# PWR.net
KiCad netlist of a schematic drawn in Altium Designer
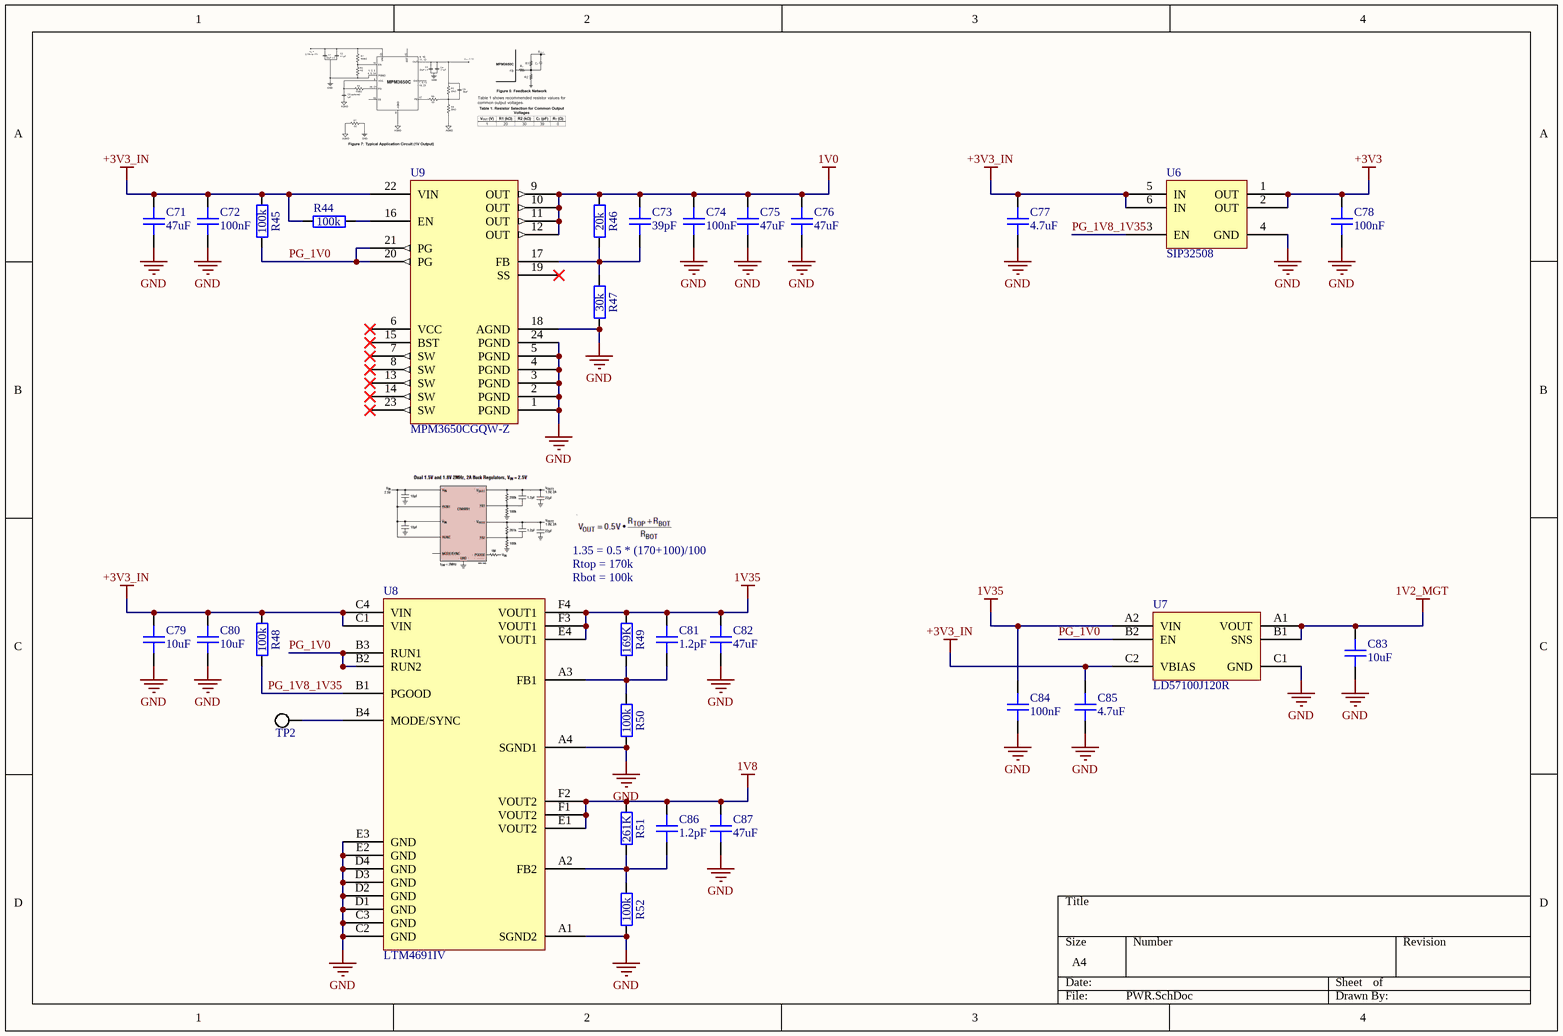
[diagram p0: PWR.SchDoc]

(export (version "E")
  (design (tool "Eeschema 10.0.6"))
  (components
    (comp (ref "C71")
      (value "47uF")
      (footprint "GEN_C_0805")
      (libsource (lib "DSO") (part "CAP 47uF 6.3V X5R 0805"))
    )
    (comp (ref "C72")
      (value "100nF")
      (footprint "GEN_C_0402")
      (libsource (lib "DSO") (part "CAP 100nF 16V X7R 0402"))
    )
    (comp (ref "C73")
      (value "39pF")
      (footprint "GEN_C_0402")
      (libsource (lib "DSO") (part "CAP 39pF 50V C0G 0402"))
    )
    (comp (ref "C74")
      (value "100nF")
      (footprint "GEN_C_0402")
      (libsource (lib "DSO") (part "CAP 100nF 16V X7R 0402"))
    )
    (comp (ref "C75")
      (value "47uF")
      (footprint "GEN_C_0805")
      (libsource (lib "DSO") (part "CAP 47uF 6.3V X5R 0805"))
    )
    (comp (ref "C76")
      (value "47uF")
      (footprint "GEN_C_0805")
      (libsource (lib "DSO") (part "CAP 47uF 6.3V X5R 0805"))
    )
    (comp (ref "C77")
      (value "4.7uF")
      (footprint "GEN_C_0402")
      (libsource (lib "DSO") (part "CAP 4.7uF 6.3V X5R 0402"))
    )
    (comp (ref "C78")
      (value "100nF")
      (footprint "GEN_C_0402")
      (libsource (lib "DSO") (part "CAP 100nF 16V X7R 0402"))
    )
    (comp (ref "C79")
      (value "10uF")
      (footprint "GEN_C_0603")
      (libsource (lib "DSO") (part "CAP 10uF 10V X5R 0603"))
    )
    (comp (ref "C80")
      (value "10uF")
      (footprint "GEN_C_0603")
      (libsource (lib "DSO") (part "CAP 10uF 10V X5R 0603"))
    )
    (comp (ref "C81")
      (value "1.2pF")
      (footprint "GEN_C_0402")
      (libsource (lib "DSO") (part "CAP 1.2pF 50V C0G 0402"))
    )
    (comp (ref "C82")
      (value "47uF")
      (footprint "GEN_C_0805")
      (libsource (lib "DSO") (part "CAP 47uF 6.3V X5R 0805"))
    )
    (comp (ref "C83")
      (value "10uF")
      (footprint "GEN_C_0603")
      (libsource (lib "DSO") (part "CAP 10uF 10V X5R 0603"))
    )
    (comp (ref "C84")
      (value "100nF")
      (footprint "GEN_C_0402")
      (libsource (lib "DSO") (part "CAP 100nF 16V X7R 0402"))
    )
    (comp (ref "C85")
      (value "4.7uF")
      (footprint "GEN_C_0402")
      (libsource (lib "DSO") (part "CAP 4.7uF 6.3V X5R 0402"))
    )
    (comp (ref "C86")
      (value "1.2pF")
      (footprint "GEN_C_0402")
      (libsource (lib "DSO") (part "CAP 1.2pF 50V C0G 0402"))
    )
    (comp (ref "C87")
      (value "47uF")
      (footprint "GEN_C_0805")
      (libsource (lib "DSO") (part "CAP 47uF 6.3V X5R 0805"))
    )
    (comp (ref "R44")
      (value "100k")
      (footprint "GEN_R_0402")
      (fields (field (name "TOLERANCE") "1%"))
      (libsource (lib "") (part "RES 100K OHM 1% 1/10W 0402_1"))
    )
    (comp (ref "R45")
      (value "100k")
      (footprint "GEN_R_0402")
      (fields (field (name "TOLERANCE") "1%"))
      (libsource (lib "DSO") (part "RES 100K OHM 1% 1/10W 0402"))
    )
    (comp (ref "R46")
      (value "20k")
      (footprint "GEN_R_0402")
      (fields (field (name "TOLERANCE") "1%"))
      (libsource (lib "DSO") (part "RES 20K OHM 1% 1/16W 0402"))
    )
    (comp (ref "R47")
      (value "30k")
      (footprint "GEN_R_0402")
      (fields (field (name "TOLERANCE") "1%"))
      (libsource (lib "DSO") (part "RES 30K OHM 1% 1/16W 0402"))
    )
    (comp (ref "R48")
      (value "100k")
      (footprint "GEN_R_0402")
      (fields (field (name "TOLERANCE") "1%"))
      (libsource (lib "DSO") (part "RES 100K OHM 1% 1/10W 0402"))
    )
    (comp (ref "R49")
      (value "169K")
      (footprint "GEN_R_0402")
      (fields (field (name "TOLERANCE") "1%"))
      (libsource (lib "DSO") (part "RES 169K OHM 1% 1/16W 0402"))
    )
    (comp (ref "R50")
      (value "100k")
      (footprint "GEN_R_0402")
      (fields (field (name "TOLERANCE") "1%"))
      (libsource (lib "DSO") (part "RES 100K OHM 1% 1/10W 0402"))
    )
    (comp (ref "R51")
      (value "261K")
      (footprint "GEN_R_0402")
      (fields (field (name "TOLERANCE") "1%"))
      (libsource (lib "DSO") (part "RES 261K OHM 1% 1/16W 0402"))
    )
    (comp (ref "R52")
      (value "100k")
      (footprint "GEN_R_0402")
      (fields (field (name "TOLERANCE") "1%"))
      (libsource (lib "DSO") (part "RES 100K OHM 1% 1/10W 0402"))
    )
    (comp (ref "TP2") (value "PCB") (footprint "GEN_TP_PCB") (libsource (lib "DSO") (part "TP PCB 1mm")))
    (comp (ref "U6")
      (value "SIP32508")
      (footprint "VISH_TSOT6")
      (libsource (lib "DSO") (part "IC SWITCH LOAD SIP32508"))
    )
    (comp (ref "U7")
      (value "LD57100J120R")
      (footprint "ST_FlipChip6")
      (libsource (lib "DSO") (part "IC LDO LD57100J120R"))
    )
    (comp (ref "U8")
      (value "LTM4691IV")
      (footprint "AD_LGA24")
      (libsource (lib "DSO") (part "IC BUCK LTM4691IV"))
    )
    (comp (ref "U9")
      (value "MPM3650CGQW-Z")
      (footprint "MPS_MPM3650")
      (libsource (lib "DSO") (part "IC BUCK MPM3650CGQW-Z"))
    )
  )
  (nets
    (net (code "1") (name "+3V3") (class "Default")
      (node (ref "C78") (pin "2") (pinfunction "2_2") (pintype "passive"))
      (node (ref "U6") (pin "1") (pinfunction "OUT_1") (pintype "passive"))
      (node (ref "U6") (pin "2") (pinfunction "OUT_2") (pintype "passive"))
    )
    (net (code "2") (name "+3V3_IN") (class "Default")
      (node (ref "C71") (pin "2") (pinfunction "2_2") (pintype "passive"))
      (node (ref "C72") (pin "2") (pinfunction "2_2") (pintype "passive"))
      (node (ref "C77") (pin "2") (pinfunction "2_2") (pintype "passive"))
      (node (ref "C79") (pin "2") (pinfunction "2_2") (pintype "passive"))
      (node (ref "C80") (pin "2") (pinfunction "2_2") (pintype "passive"))
      (node (ref "C85") (pin "2") (pinfunction "2_2") (pintype "passive"))
      (node (ref "R44") (pin "1") (pinfunction "1_1") (pintype "passive"))
      (node (ref "R45") (pin "2") (pinfunction "2_2") (pintype "passive"))
      (node (ref "R48") (pin "2") (pinfunction "2_2") (pintype "passive"))
      (node (ref "U6") (pin "5") (pinfunction "IN_5") (pintype "passive"))
      (node (ref "U6") (pin "6") (pinfunction "IN_6") (pintype "passive"))
      (node (ref "U7") (pin "C2") (pinfunction "VBIAS_C2") (pintype "passive"))
      (node (ref "U8") (pin "C1") (pinfunction "VIN_C1") (pintype "passive"))
      (node (ref "U8") (pin "C4") (pinfunction "VIN_C4") (pintype "passive"))
      (node (ref "U9") (pin "22") (pinfunction "VIN_22") (pintype "power_in"))
    )
    (net (code "3") (name "/PG_1V0") (class "Default")
      (node (ref "R45") (pin "1") (pinfunction "1_1") (pintype "passive"))
      (node (ref "U7") (pin "B2") (pinfunction "EN_B2") (pintype "passive"))
      (node (ref "U8") (pin "B2") (pinfunction "RUN2_B2") (pintype "passive"))
      (node (ref "U8") (pin "B3") (pinfunction "RUN1_B3") (pintype "passive"))
      (node (ref "U9") (pin "20") (pinfunction "PG_20") (pintype "output"))
      (node (ref "U9") (pin "21") (pinfunction "PG_21") (pintype "output"))
    )
    (net (code "4") (name "/PG_1V8_1V35") (class "Default")
      (node (ref "R48") (pin "1") (pinfunction "1_1") (pintype "passive"))
      (node (ref "U6") (pin "3") (pinfunction "EN_3") (pintype "passive"))
      (node (ref "U8") (pin "B1") (pinfunction "PGOOD_B1") (pintype "passive"))
    )
    (net (code "5") (name "1V0") (class "Default")
      (node (ref "C73") (pin "2") (pinfunction "2_2") (pintype "passive"))
      (node (ref "C74") (pin "2") (pinfunction "2_2") (pintype "passive"))
      (node (ref "C75") (pin "2") (pinfunction "2_2") (pintype "passive"))
      (node (ref "C76") (pin "2") (pinfunction "2_2") (pintype "passive"))
      (node (ref "R46") (pin "2") (pinfunction "2_2") (pintype "passive"))
      (node (ref "U9") (pin "10") (pinfunction "OUT_10") (pintype "output"))
      (node (ref "U9") (pin "11") (pinfunction "OUT_11") (pintype "output"))
      (node (ref "U9") (pin "12") (pinfunction "OUT_12") (pintype "output"))
      (node (ref "U9") (pin "9") (pinfunction "OUT_9") (pintype "output"))
    )
    (net (code "6") (name "1V2_MGT") (class "Default")
      (node (ref "C83") (pin "2") (pinfunction "2_2") (pintype "passive"))
      (node (ref "U7") (pin "A1") (pinfunction "VOUT_A1") (pintype "passive"))
      (node (ref "U7") (pin "B1") (pinfunction "SNS_B1") (pintype "passive"))
    )
    (net (code "7") (name "1V8") (class "Default")
      (node (ref "C86") (pin "2") (pinfunction "2_2") (pintype "passive"))
      (node (ref "C87") (pin "2") (pinfunction "2_2") (pintype "passive"))
      (node (ref "R51") (pin "2") (pinfunction "2_2") (pintype "passive"))
      (node (ref "U8") (pin "E1") (pinfunction "VOUT2_E1") (pintype "passive"))
      (node (ref "U8") (pin "F1") (pinfunction "VOUT2_F1") (pintype "passive"))
      (node (ref "U8") (pin "F2") (pinfunction "VOUT2_F2") (pintype "passive"))
    )
    (net (code "8") (name "1V35") (class "Default")
      (node (ref "C81") (pin "2") (pinfunction "2_2") (pintype "passive"))
      (node (ref "C82") (pin "2") (pinfunction "2_2") (pintype "passive"))
      (node (ref "C84") (pin "2") (pinfunction "2_2") (pintype "passive"))
      (node (ref "R49") (pin "2") (pinfunction "2_2") (pintype "passive"))
      (node (ref "U7") (pin "A2") (pinfunction "VIN_A2") (pintype "passive"))
      (node (ref "U8") (pin "E4") (pinfunction "VOUT1_E4") (pintype "passive"))
      (node (ref "U8") (pin "F3") (pinfunction "VOUT1_F3") (pintype "passive"))
      (node (ref "U8") (pin "F4") (pinfunction "VOUT1_F4") (pintype "passive"))
    )
    (net (code "9") (name "GND") (class "Default")
      (node (ref "C71") (pin "1") (pinfunction "1_1") (pintype "passive"))
      (node (ref "C72") (pin "1") (pinfunction "1_1") (pintype "passive"))
      (node (ref "C74") (pin "1") (pinfunction "1_1") (pintype "passive"))
      (node (ref "C75") (pin "1") (pinfunction "1_1") (pintype "passive"))
      (node (ref "C76") (pin "1") (pinfunction "1_1") (pintype "passive"))
      (node (ref "C77") (pin "1") (pinfunction "1_1") (pintype "passive"))
      (node (ref "C78") (pin "1") (pinfunction "1_1") (pintype "passive"))
      (node (ref "C79") (pin "1") (pinfunction "1_1") (pintype "passive"))
      (node (ref "C80") (pin "1") (pinfunction "1_1") (pintype "passive"))
      (node (ref "C82") (pin "1") (pinfunction "1_1") (pintype "passive"))
      (node (ref "C83") (pin "1") (pinfunction "1_1") (pintype "passive"))
      (node (ref "C84") (pin "1") (pinfunction "1_1") (pintype "passive"))
      (node (ref "C85") (pin "1") (pinfunction "1_1") (pintype "passive"))
      (node (ref "C87") (pin "1") (pinfunction "1_1") (pintype "passive"))
      (node (ref "R47") (pin "1") (pinfunction "1_1") (pintype "passive"))
      (node (ref "R50") (pin "1") (pinfunction "1_1") (pintype "passive"))
      (node (ref "R52") (pin "1") (pinfunction "1_1") (pintype "passive"))
      (node (ref "U6") (pin "4") (pinfunction "GND_4") (pintype "passive"))
      (node (ref "U7") (pin "C1") (pinfunction "GND_C1") (pintype "passive"))
      (node (ref "U8") (pin "A1") (pinfunction "SGND2_A1") (pintype "passive"))
      (node (ref "U8") (pin "A4") (pinfunction "SGND1_A4") (pintype "passive"))
      (node (ref "U8") (pin "C2") (pinfunction "GND_C2") (pintype "passive"))
      (node (ref "U8") (pin "C3") (pinfunction "GND_C3") (pintype "passive"))
      (node (ref "U8") (pin "D1") (pinfunction "GND_D1") (pintype "passive"))
      (node (ref "U8") (pin "D2") (pinfunction "GND_D2") (pintype "passive"))
      (node (ref "U8") (pin "D3") (pinfunction "GND_D3") (pintype "passive"))
      (node (ref "U8") (pin "D4") (pinfunction "GND_D4") (pintype "passive"))
      (node (ref "U8") (pin "E2") (pinfunction "GND_E2") (pintype "passive"))
      (node (ref "U8") (pin "E3") (pinfunction "GND_E3") (pintype "passive"))
      (node (ref "U9") (pin "1") (pinfunction "PGND_1") (pintype "passive"))
      (node (ref "U9") (pin "18") (pinfunction "AGND_18") (pintype "passive"))
      (node (ref "U9") (pin "2") (pinfunction "PGND_2") (pintype "passive"))
      (node (ref "U9") (pin "24") (pinfunction "PGND_24") (pintype "passive"))
      (node (ref "U9") (pin "3") (pinfunction "PGND_3") (pintype "passive"))
      (node (ref "U9") (pin "4") (pinfunction "PGND_4") (pintype "passive"))
      (node (ref "U9") (pin "5") (pinfunction "PGND_5") (pintype "passive"))
    )
    (net (code "10") (name "Net-(U8-FB1)") (class "Default")
      (node (ref "C81") (pin "1") (pinfunction "1_1") (pintype "passive"))
      (node (ref "R49") (pin "1") (pinfunction "1_1") (pintype "passive"))
      (node (ref "R50") (pin "2") (pinfunction "2_2") (pintype "passive"))
      (node (ref "U8") (pin "A3") (pinfunction "FB1_A3") (pintype "passive"))
    )
    (net (code "11") (name "Net-(U8-FB2)") (class "Default")
      (node (ref "C86") (pin "1") (pinfunction "1_1") (pintype "passive"))
      (node (ref "R51") (pin "1") (pinfunction "1_1") (pintype "passive"))
      (node (ref "R52") (pin "2") (pinfunction "2_2") (pintype "passive"))
      (node (ref "U8") (pin "A2") (pinfunction "FB2_A2") (pintype "passive"))
    )
    (net (code "12") (name "Net-(U8-MODE{slash}SYNC)") (class "Default")
      (node (ref "TP2") (pin "1") (pinfunction "1_1") (pintype "passive"))
      (node (ref "U8") (pin "B4") (pinfunction "MODE/SYNC_B4") (pintype "passive"))
    )
    (net (code "13") (name "Net-(U9-EN)") (class "Default")
      (node (ref "R44") (pin "2") (pinfunction "2_2") (pintype "passive"))
      (node (ref "U9") (pin "16") (pinfunction "EN_16") (pintype "passive"))
    )
    (net (code "14") (name "Net-(U9-FB)") (class "Default")
      (node (ref "C73") (pin "1") (pinfunction "1_1") (pintype "passive"))
      (node (ref "R46") (pin "1") (pinfunction "1_1") (pintype "passive"))
      (node (ref "R47") (pin "2") (pinfunction "2_2") (pintype "passive"))
      (node (ref "U9") (pin "17") (pinfunction "FB_17") (pintype "passive"))
    )
    (net (code "15") (name "unconnected-(U9-BST-Pad15)") (class "Default")
      (node (ref "U9") (pin "15") (pinfunction "BST_15") (pintype "passive+no_connect"))
    )
    (net (code "16") (name "unconnected-(U9-SS-Pad19)") (class "Default")
      (node (ref "U9") (pin "19") (pinfunction "SS_19") (pintype "passive+no_connect"))
    )
    (net (code "17") (name "unconnected-(U9-SW-Pad7)") (class "Default")
      (node (ref "U9") (pin "7") (pinfunction "SW_7") (pintype "output+no_connect"))
    )
    (net (code "18") (name "unconnected-(U9-SW-Pad8)") (class "Default")
      (node (ref "U9") (pin "8") (pinfunction "SW_8") (pintype "output+no_connect"))
    )
    (net (code "19") (name "unconnected-(U9-SW-Pad13)") (class "Default")
      (node (ref "U9") (pin "13") (pinfunction "SW_13") (pintype "output+no_connect"))
    )
    (net (code "20") (name "unconnected-(U9-SW-Pad14)") (class "Default")
      (node (ref "U9") (pin "14") (pinfunction "SW_14") (pintype "output+no_connect"))
    )
    (net (code "21") (name "unconnected-(U9-SW-Pad23)") (class "Default")
      (node (ref "U9") (pin "23") (pinfunction "SW_23") (pintype "output+no_connect"))
    )
    (net (code "22") (name "unconnected-(U9-VCC-Pad6)") (class "Default")
      (node (ref "U9") (pin "6") (pinfunction "VCC_6") (pintype "power_in+no_connect"))
    )
  )
)
